# mku_16_ch.net
KiCad netlist of a schematic drawn in Altium Designer
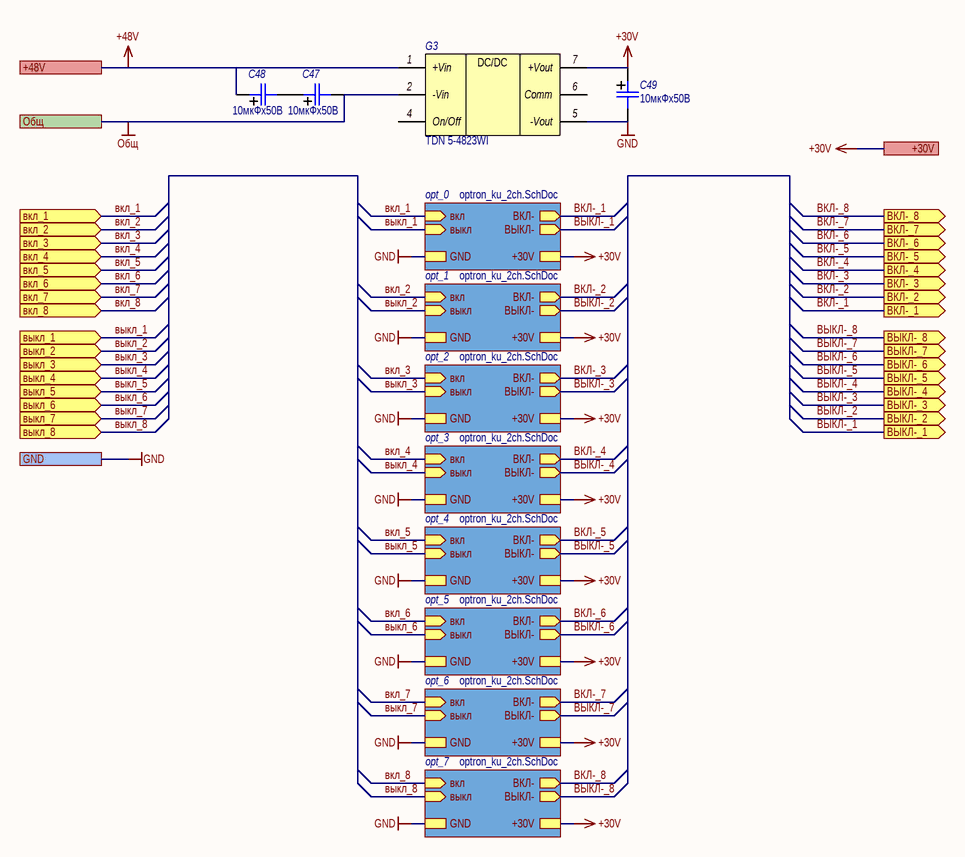
[diagram p0: mku_16_ch.SchDoc]

(export (version "E")
  (design (tool "Eeschema 10.0.6"))
  (components
    (comp (ref "C47")
      (value "10мкФх50В")
      (footprint "SMD_size_C")
      (description "Polarized capacitor")
      (libsource (lib "Passive") (part "Capacitor_pol"))
    )
    (comp (ref "C48")
      (value "10мкФх50В")
      (footprint "SMD_size_C")
      (description "Polarized capacitor")
      (libsource (lib "Passive") (part "Capacitor_pol"))
    )
    (comp (ref "C49")
      (value "10мкФх50В")
      (footprint "SMD_size_C")
      (description "Polarized capacitor")
      (libsource (lib "Passive") (part "Capacitor_pol"))
    )
    (comp (ref "G3")
      (value "TDN 5-4821")
      (footprint "TDN_5_WISM")
      (description "DC/DC converter")
      (fields (field (name "НАИМЕНОВАНИЕ") "TDN 5-4823WI"))
      (libsource (lib "TDN_5") (part "TDN_5"))
    )
  )
  (nets
    (net (code "1") (name "+30V") (class "Default")
      (node (ref "C49") (pin "1") (pinfunction "1_1") (pintype "passive"))
      (node (ref "G3") (pin "7") (pinfunction "+Vout_7") (pintype "power_in"))
    )
    (net (code "2") (name "+48V") (class "Default")
      (node (ref "C48") (pin "1") (pinfunction "1_1") (pintype "passive"))
      (node (ref "G3") (pin "1") (pinfunction "+Vin_1") (pintype "power_in"))
    )
    (net (code "35") (name "GND") (class "Default")
      (node (ref "C49") (pin "2") (pinfunction "2_2") (pintype "passive"))
      (node (ref "G3") (pin "5") (pinfunction "-Vout_5") (pintype "power_in"))
    )
    (net (code "36") (name "Net-(C47-Pad1)") (class "Default")
      (node (ref "C47") (pin "1") (pinfunction "1_1") (pintype "passive"))
      (node (ref "C48") (pin "2") (pinfunction "2_2") (pintype "passive"))
    )
    (net (code "37") (name "unconnected-(G3-Comm-Pad6)") (class "Default")
      (node (ref "G3") (pin "6") (pinfunction "Comm_6") (pintype "power_in"))
    )
    (net (code "38") (name "unconnected-(G3-On{slash}Off-Pad4)") (class "Default")
      (node (ref "G3") (pin "4") (pinfunction "On/Off_4") (pintype "open_collector"))
    )
    (net (code "39") (name "Общ") (class "Default")
      (node (ref "C47") (pin "2") (pinfunction "2_2") (pintype "passive"))
      (node (ref "G3") (pin "2") (pinfunction "-Vin_2") (pintype "power_in"))
    )
  )
)
